# jphy_pwr_v1.net
KiCad netlist of a schematic drawn in EAGLE
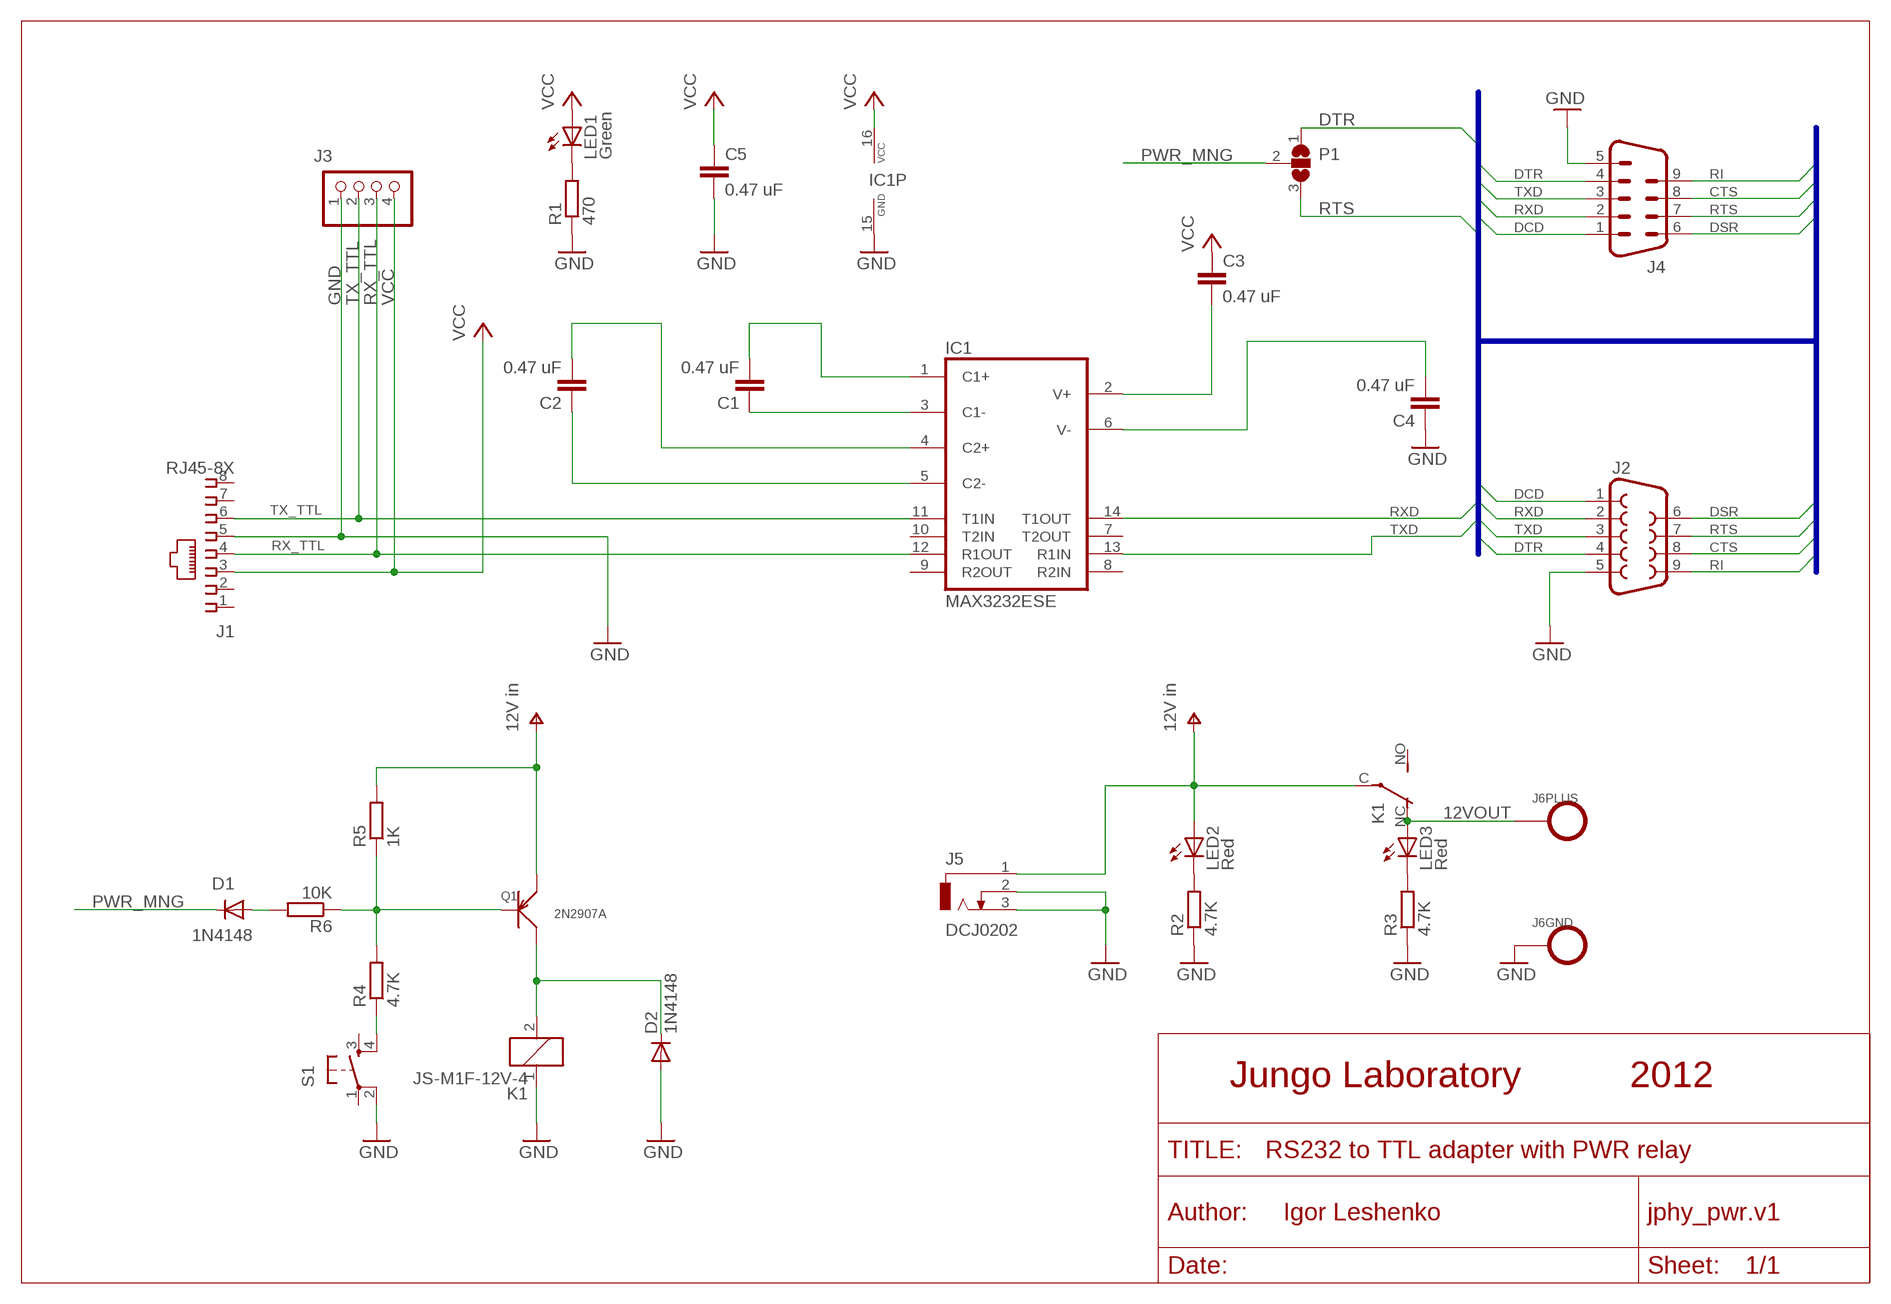
[diagram p0: schematic, sheet 1]

(export (version "E")
  (design (tool "Eeschema 10.0.6"))
  (components
    (comp (ref "C1")
      (value "0.47 uF")
      (footprint "eagle-import:C0805")
      (libsource (lib "eagle-import") (part "C-EUC0805"))
    )
    (comp (ref "C2")
      (value "0.47 uF")
      (footprint "eagle-import:C0805")
      (libsource (lib "eagle-import") (part "C-EUC0805"))
    )
    (comp (ref "C3")
      (value "0.47 uF")
      (footprint "eagle-import:C0805")
      (libsource (lib "eagle-import") (part "C-EUC0805"))
    )
    (comp (ref "C4")
      (value "0.47 uF")
      (footprint "eagle-import:C0805")
      (libsource (lib "eagle-import") (part "C-EUC0805"))
    )
    (comp (ref "C5")
      (value "0.47 uF")
      (footprint "eagle-import:C1206")
      (libsource (lib "eagle-import") (part "C-EUC1206"))
    )
    (comp (ref "D1")
      (value "1N4148")
      (footprint "eagle-import:D-5")
      (libsource (lib "eagle-import") (part "DIODE-D-5"))
    )
    (comp (ref "D2")
      (value "1N4148")
      (footprint "eagle-import:D-5")
      (libsource (lib "eagle-import") (part "DIODE-D-5"))
    )
    (comp (ref "IC1")
      (value "MAX3232ESE")
      (footprint "eagle-import:SO16")
      (fields (field (name "MF") "MAXIM"))
      (libsource (lib "eagle-import") (part "MAX3232SEE"))
    )
    (comp (ref "J1")
      (value "RJ45-8X")
      (footprint "eagle-import:RJ45-NO-SHIELD")
      (libsource (lib "eagle-import") (part "RJ45-8X"))
    )
    (comp (ref "J2")
      (value "F09D")
      (footprint "eagle-import:F09D")
      (libsource (lib "eagle-import") (part "F09D"))
    )
    (comp (ref "J3")
      (value "PINHD-1X4")
      (footprint "eagle-import:1X04")
      (libsource (lib "eagle-import") (part "PINHD-1X4"))
    )
    (comp (ref "J4")
      (value "M09D")
      (footprint "eagle-import:M09D")
      (libsource (lib "eagle-import") (part "M09D"))
    )
    (comp (ref "J5")
      (value "DCJ0202")
      (footprint "eagle-import:DCJ0202")
      (libsource (lib "eagle-import") (part "DCJ0202"))
    )
    (comp (ref "J6")
      (value "POWER-OUT")
      (footprint "eagle-import:FLEX-POWER")
      (libsource (lib "eagle-import") (part "POWER-OUT"))
    )
    (comp (ref "K1")
      (value "JS-M1F-12V-4")
      (footprint "eagle-import:JS-M")
      (libsource (lib "eagle-import") (part "JS-M1F-12V-4"))
    )
    (comp (ref "LED1")
      (value "Green")
      (footprint "eagle-import:LED3MM")
      (libsource (lib "eagle-import") (part "LED3MM"))
    )
    (comp (ref "LED2")
      (value "Red")
      (footprint "eagle-import:LED3MM")
      (libsource (lib "eagle-import") (part "LED3MM"))
    )
    (comp (ref "LED3")
      (value "Red")
      (footprint "eagle-import:LED3MM")
      (libsource (lib "eagle-import") (part "LED3MM"))
    )
    (comp (ref "P1")
      (value "PAD-SOLDERJUMPER-2WAYT")
      (footprint "eagle-import:3P-SMD-4.8X2")
      (libsource (lib "eagle-import") (part "PAD-SOLDERJUMPER-2WAYT"))
    )
    (comp (ref "Q1")
      (value "2N2907A")
      (footprint "eagle-import:TO-92-TRIANGLE")
      (libsource (lib "eagle-import") (part "TRANSISTOR-PNP-TO-92"))
    )
    (comp (ref "R1")
      (value "470")
      (footprint "eagle-import:0207_2V")
      (libsource (lib "eagle-import") (part "R-EU_0207/2V"))
    )
    (comp (ref "R2")
      (value "4.7K")
      (footprint "eagle-import:0207_2V")
      (libsource (lib "eagle-import") (part "R-EU_0207/2V"))
    )
    (comp (ref "R3")
      (value "4.7K")
      (footprint "eagle-import:0207_2V")
      (libsource (lib "eagle-import") (part "R-EU_0207/2V"))
    )
    (comp (ref "R4")
      (value "4.7K")
      (footprint "eagle-import:0207_2V")
      (libsource (lib "eagle-import") (part "R-EU_0207/2V"))
    )
    (comp (ref "R5")
      (value "1K")
      (footprint "eagle-import:0207_2V")
      (libsource (lib "eagle-import") (part "R-EU_0207/2V"))
    )
    (comp (ref "R6")
      (value "10K")
      (footprint "eagle-import:0207_2V")
      (libsource (lib "eagle-import") (part "R-EU_0207/2V"))
    )
    (comp (ref "S1")
      (value "TAC_SWITCHPTH")
      (footprint "eagle-import:TACTILE-PTH")
      (libsource (lib "eagle-import") (part "TAC_SWITCHPTH"))
    )
  )
  (nets
    (net (code "1") (name "/12VOUT") (class "Default")
      (node (ref "J6") (pin "1") (pinfunction "P$1_1") (pintype "bidirectional"))
      (node (ref "K1") (pin "NC") (pinfunction "O_NC") (pintype "passive"))
      (node (ref "LED3") (pin "A") (pinfunction "A_A") (pintype "passive"))
    )
    (net (code "2") (name "/CTS") (class "Default")
      (node (ref "J2") (pin "8") (pinfunction "8_8") (pintype "passive"))
      (node (ref "J4") (pin "8") (pinfunction "8_8") (pintype "passive"))
    )
    (net (code "3") (name "/DCD") (class "Default")
      (node (ref "J2") (pin "1") (pinfunction "1_1") (pintype "passive"))
      (node (ref "J4") (pin "1") (pinfunction "1_1") (pintype "passive"))
    )
    (net (code "4") (name "/DSR") (class "Default")
      (node (ref "J2") (pin "6") (pinfunction "6_6") (pintype "passive"))
      (node (ref "J4") (pin "6") (pinfunction "6_6") (pintype "passive"))
    )
    (net (code "5") (name "/DTR") (class "Default")
      (node (ref "J2") (pin "4") (pinfunction "4_4") (pintype "passive"))
      (node (ref "J4") (pin "4") (pinfunction "4_4") (pintype "passive"))
      (node (ref "P1") (pin "1") (pinfunction "1_1") (pintype "passive"))
    )
    (net (code "6") (name "/PWR_MNG") (class "Default")
      (node (ref "D1") (pin "C") (pinfunction "C_C") (pintype "passive"))
      (node (ref "P1") (pin "2") (pinfunction "2_2") (pintype "passive"))
    )
    (net (code "7") (name "/RI") (class "Default")
      (node (ref "J2") (pin "9") (pinfunction "9_9") (pintype "passive"))
      (node (ref "J4") (pin "9") (pinfunction "9_9") (pintype "passive"))
    )
    (net (code "8") (name "/RTS") (class "Default")
      (node (ref "J2") (pin "7") (pinfunction "7_7") (pintype "passive"))
      (node (ref "J4") (pin "7") (pinfunction "7_7") (pintype "passive"))
      (node (ref "P1") (pin "3") (pinfunction "3_3") (pintype "passive"))
    )
    (net (code "9") (name "/RXD") (class "Default")
      (node (ref "IC1") (pin "14") (pinfunction "T1OUT_14") (pintype "output"))
      (node (ref "J2") (pin "2") (pinfunction "2_2") (pintype "passive"))
      (node (ref "J4") (pin "2") (pinfunction "2_2") (pintype "passive"))
    )
    (net (code "10") (name "/RX_TTL") (class "Default")
      (node (ref "IC1") (pin "12") (pinfunction "R1OUT_12") (pintype "output"))
      (node (ref "J1") (pin "4") (pinfunction "4_4") (pintype "passive"))
      (node (ref "J3") (pin "3") (pinfunction "3_3") (pintype "passive"))
    )
    (net (code "11") (name "/TXD") (class "Default")
      (node (ref "IC1") (pin "13") (pinfunction "R1IN_13") (pintype "input"))
      (node (ref "J2") (pin "3") (pinfunction "3_3") (pintype "passive"))
      (node (ref "J4") (pin "3") (pinfunction "3_3") (pintype "passive"))
    )
    (net (code "12") (name "/TX_TTL") (class "Default")
      (node (ref "IC1") (pin "11") (pinfunction "T1IN_11") (pintype "input"))
      (node (ref "J1") (pin "6") (pinfunction "6_6") (pintype "passive"))
      (node (ref "J3") (pin "2") (pinfunction "2_2") (pintype "passive"))
    )
    (net (code "13") (name "12V in") (class "Default")
      (node (ref "J5") (pin "1") (pinfunction "1_1") (pintype "passive"))
      (node (ref "K1") (pin "C") (pinfunction "P_C") (pintype "passive"))
      (node (ref "LED2") (pin "A") (pinfunction "A_A") (pintype "passive"))
      (node (ref "Q1") (pin "1") (pinfunction "E_1") (pintype "passive"))
      (node (ref "R5") (pin "2") (pinfunction "2_2") (pintype "passive"))
    )
    (net (code "14") (name "GND") (class "Default")
      (node (ref "C4") (pin "1") (pinfunction "1_1") (pintype "passive"))
      (node (ref "C5") (pin "2") (pinfunction "2_2") (pintype "passive"))
      (node (ref "D2") (pin "A") (pinfunction "A_A") (pintype "passive"))
      (node (ref "IC1") (pin "15") (pinfunction "GND_15") (pintype "power_in"))
      (node (ref "J1") (pin "5") (pinfunction "5_5") (pintype "passive"))
      (node (ref "J2") (pin "5") (pinfunction "5_5") (pintype "passive"))
      (node (ref "J3") (pin "1") (pinfunction "1_1") (pintype "passive"))
      (node (ref "J4") (pin "5") (pinfunction "5_5") (pintype "passive"))
      (node (ref "J5") (pin "2") (pinfunction "2_2") (pintype "passive"))
      (node (ref "J5") (pin "3") (pinfunction "3_3") (pintype "passive"))
      (node (ref "J6") (pin "2") (pinfunction "P$1_2") (pintype "bidirectional"))
      (node (ref "K1") (pin "1") (pinfunction "1_1") (pintype "passive"))
      (node (ref "R1") (pin "1") (pinfunction "1_1") (pintype "passive"))
      (node (ref "R2") (pin "1") (pinfunction "1_1") (pintype "passive"))
      (node (ref "R3") (pin "1") (pinfunction "1_1") (pintype "passive"))
      (node (ref "S1") (pin "2") (pinfunction "2_2") (pintype "passive"))
    )
    (net (code "15") (name "Net-(D1-PadA)") (class "Default")
      (node (ref "D1") (pin "A") (pinfunction "A_A") (pintype "passive"))
      (node (ref "R6") (pin "2") (pinfunction "2_2") (pintype "passive"))
    )
    (net (code "16") (name "Net-(IC1A-C1+)") (class "Default")
      (node (ref "C1") (pin "2") (pinfunction "2_2") (pintype "passive"))
      (node (ref "IC1") (pin "1") (pinfunction "C1+_1") (pintype "bidirectional"))
    )
    (net (code "17") (name "Net-(IC1A-C1-)") (class "Default")
      (node (ref "C1") (pin "1") (pinfunction "1_1") (pintype "passive"))
      (node (ref "IC1") (pin "3") (pinfunction "C1-_3") (pintype "bidirectional"))
    )
    (net (code "18") (name "Net-(IC1A-C2+)") (class "Default")
      (node (ref "C2") (pin "2") (pinfunction "2_2") (pintype "passive"))
      (node (ref "IC1") (pin "4") (pinfunction "C2+_4") (pintype "bidirectional"))
    )
    (net (code "19") (name "Net-(IC1A-C2-)") (class "Default")
      (node (ref "C2") (pin "1") (pinfunction "1_1") (pintype "passive"))
      (node (ref "IC1") (pin "5") (pinfunction "C2-_5") (pintype "bidirectional"))
    )
    (net (code "20") (name "Net-(IC1A-V+)") (class "Default")
      (node (ref "C3") (pin "2") (pinfunction "2_2") (pintype "passive"))
      (node (ref "IC1") (pin "2") (pinfunction "V+_2") (pintype "bidirectional"))
    )
    (net (code "21") (name "Net-(IC1A-V-)") (class "Default")
      (node (ref "C4") (pin "2") (pinfunction "2_2") (pintype "passive"))
      (node (ref "IC1") (pin "6") (pinfunction "V-_6") (pintype "bidirectional"))
    )
    (net (code "22") (name "Net-(LED1-C)") (class "Default")
      (node (ref "LED1") (pin "K") (pinfunction "C_K") (pintype "passive"))
      (node (ref "R1") (pin "2") (pinfunction "2_2") (pintype "passive"))
    )
    (net (code "23") (name "Net-(LED2-C)") (class "Default")
      (node (ref "LED2") (pin "K") (pinfunction "C_K") (pintype "passive"))
      (node (ref "R2") (pin "2") (pinfunction "2_2") (pintype "passive"))
    )
    (net (code "24") (name "Net-(LED3-C)") (class "Default")
      (node (ref "LED3") (pin "K") (pinfunction "C_K") (pintype "passive"))
      (node (ref "R3") (pin "2") (pinfunction "2_2") (pintype "passive"))
    )
    (net (code "25") (name "Net-(Q1-B)") (class "Default")
      (node (ref "Q1") (pin "2") (pinfunction "B_2") (pintype "passive"))
      (node (ref "R4") (pin "2") (pinfunction "2_2") (pintype "passive"))
      (node (ref "R5") (pin "1") (pinfunction "1_1") (pintype "passive"))
      (node (ref "R6") (pin "1") (pinfunction "1_1") (pintype "passive"))
    )
    (net (code "26") (name "Net-(Q1-C)") (class "Default")
      (node (ref "D2") (pin "C") (pinfunction "C_C") (pintype "passive"))
      (node (ref "K1") (pin "2") (pinfunction "2_2") (pintype "passive"))
      (node (ref "Q1") (pin "3") (pinfunction "C_3") (pintype "passive"))
    )
    (net (code "27") (name "Net-(R4-Pad1)") (class "Default")
      (node (ref "R4") (pin "1") (pinfunction "1_1") (pintype "passive"))
      (node (ref "S1") (pin "4") (pinfunction "4_4") (pintype "passive"))
    )
    (net (code "28") (name "VCC") (class "Default")
      (node (ref "C3") (pin "1") (pinfunction "1_1") (pintype "passive"))
      (node (ref "C5") (pin "1") (pinfunction "1_1") (pintype "passive"))
      (node (ref "IC1") (pin "16") (pinfunction "VCC_16") (pintype "power_in"))
      (node (ref "J1") (pin "3") (pinfunction "3_3") (pintype "passive"))
      (node (ref "J3") (pin "4") (pinfunction "4_4") (pintype "passive"))
      (node (ref "LED1") (pin "A") (pinfunction "A_A") (pintype "passive"))
    )
    (net (code "29") (name "unconnected-(IC1A-R2IN-Pad8)") (class "Default")
      (node (ref "IC1") (pin "8") (pinfunction "R2IN_8") (pintype "input"))
    )
    (net (code "30") (name "unconnected-(IC1A-R2OUT-Pad9)") (class "Default")
      (node (ref "IC1") (pin "9") (pinfunction "R2OUT_9") (pintype "output"))
    )
    (net (code "31") (name "unconnected-(IC1A-T2IN-Pad10)") (class "Default")
      (node (ref "IC1") (pin "10") (pinfunction "T2IN_10") (pintype "input"))
    )
    (net (code "32") (name "unconnected-(IC1A-T2OUT-Pad7)") (class "Default")
      (node (ref "IC1") (pin "7") (pinfunction "T2OUT_7") (pintype "output"))
    )
    (net (code "33") (name "unconnected-(J1-Pad1)") (class "Default")
      (node (ref "J1") (pin "1") (pinfunction "1_1") (pintype "passive"))
    )
    (net (code "34") (name "unconnected-(J1-Pad2)") (class "Default")
      (node (ref "J1") (pin "2") (pinfunction "2_2") (pintype "passive"))
    )
    (net (code "35") (name "unconnected-(J1-Pad7)") (class "Default")
      (node (ref "J1") (pin "7") (pinfunction "7_7") (pintype "passive"))
    )
    (net (code "36") (name "unconnected-(J1-Pad8)") (class "Default")
      (node (ref "J1") (pin "8") (pinfunction "8_8") (pintype "passive"))
    )
    (net (code "37") (name "unconnected-(K1B-S-PadNO)") (class "Default")
      (node (ref "K1") (pin "NO") (pinfunction "S_NO") (pintype "passive"))
    )
    (net (code "38") (name "unconnected-(S1-Pad1)") (class "Default")
      (node (ref "S1") (pin "1") (pinfunction "1_1") (pintype "passive"))
    )
    (net (code "39") (name "unconnected-(S1-Pad3)") (class "Default")
      (node (ref "S1") (pin "3") (pinfunction "3_3") (pintype "passive"))
    )
  )
)
